# OneWireGateway_2x_0_2.net
KiCad netlist of a schematic drawn in EAGLE
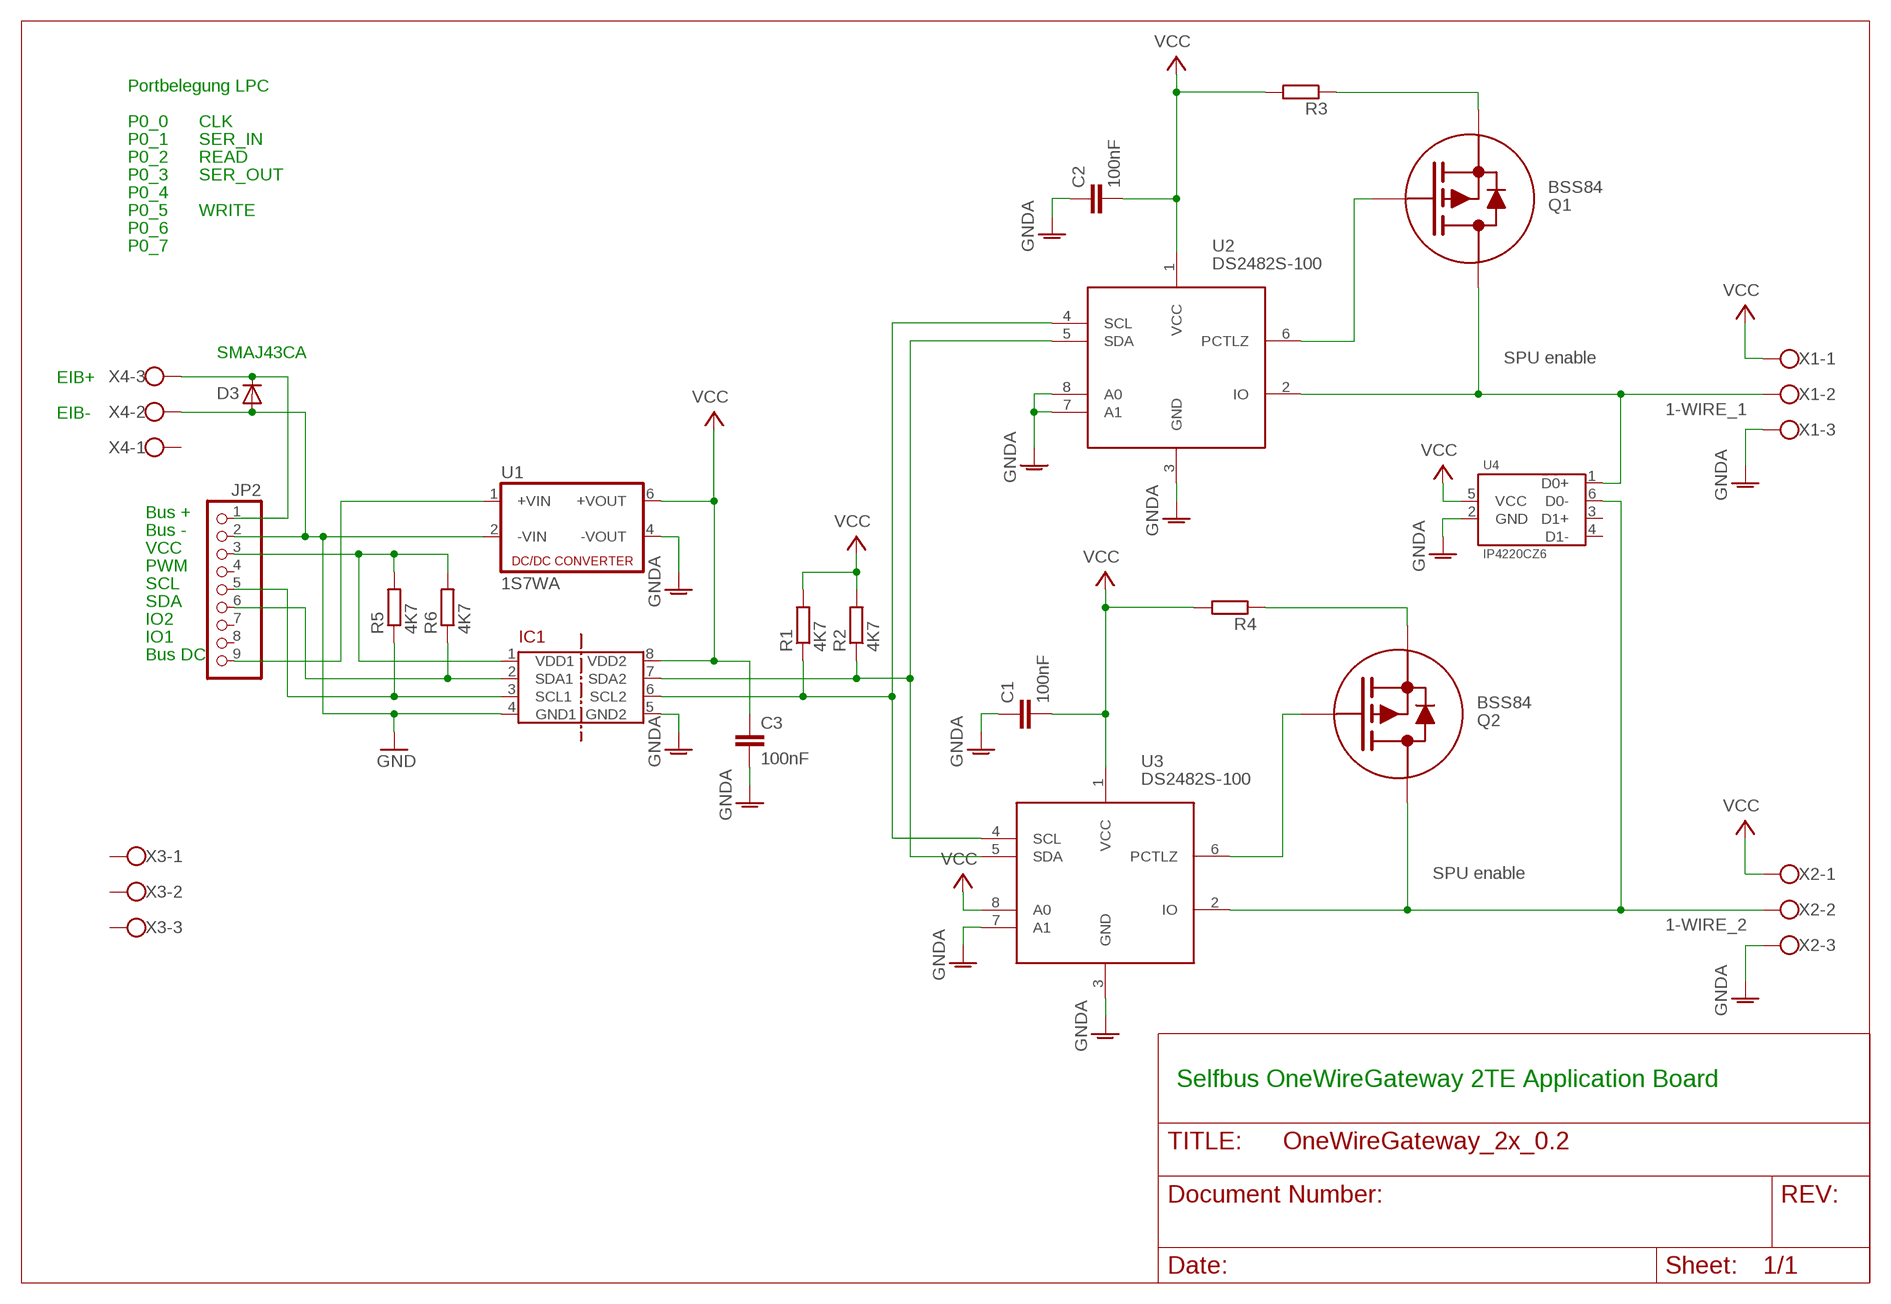
[diagram p0: schematic, sheet 1]

(export (version "E")
  (design (tool "Eeschema 10.0.6"))
  (components
    (comp (ref "C1")
      (value "100nF")
      (footprint "eagle-import:C0805")
      (libsource (lib "eagle-import") (part "C-EUC0805"))
    )
    (comp (ref "C2")
      (value "100nF")
      (footprint "eagle-import:C0805")
      (libsource (lib "eagle-import") (part "C-EUC0805"))
    )
    (comp (ref "C3")
      (value "100nF")
      (footprint "eagle-import:C0805")
      (libsource (lib "eagle-import") (part "C-EUC0805"))
    )
    (comp (ref "D3")
      (value "D-SMB")
      (footprint "eagle-import:SMB")
      (libsource (lib "eagle-import") (part "D-SMB"))
    )
    (comp (ref "IC1")
      (value "ADUM1250")
      (footprint "eagle-import:SO08")
      (libsource (lib "eagle-import") (part "ADUM1250"))
    )
    (comp (ref "JP2")
      (value "PINHD-1X9")
      (footprint "eagle-import:1X09")
      (libsource (lib "eagle-import") (part "PINHD-1X9"))
    )
    (comp (ref "Q1")
      (value "BSS84")
      (footprint "eagle-import:SOT-23-3")
      (fields (field (name "MF") "Fairchild Semiconductor"))
      (libsource (lib "eagle-import") (part "BSS841"))
    )
    (comp (ref "Q2")
      (value "BSS84")
      (footprint "eagle-import:SOT-23-3")
      (fields (field (name "MF") "Fairchild Semiconductor"))
      (libsource (lib "eagle-import") (part "BSS841"))
    )
    (comp (ref "R1")
      (value "4K7")
      (footprint "eagle-import:R0805")
      (libsource (lib "eagle-import") (part "R-EU_R0805"))
    )
    (comp (ref "R2")
      (value "4K7")
      (footprint "eagle-import:R0805")
      (libsource (lib "eagle-import") (part "R-EU_R0805"))
    )
    (comp (ref "R3")
      (value "R-EU_R0805")
      (footprint "eagle-import:R0805")
      (libsource (lib "eagle-import") (part "R-EU_R0805"))
    )
    (comp (ref "R4")
      (value "R-EU_R0805")
      (footprint "eagle-import:R0805")
      (libsource (lib "eagle-import") (part "R-EU_R0805"))
    )
    (comp (ref "R5")
      (value "4K7")
      (footprint "eagle-import:R0805")
      (libsource (lib "eagle-import") (part "R-EU_R0805"))
    )
    (comp (ref "R6")
      (value "4K7")
      (footprint "eagle-import:R0805")
      (libsource (lib "eagle-import") (part "R-EU_R0805"))
    )
    (comp (ref "U1")
      (value "1S7WA")
      (footprint "eagle-import:7PIN_SIP")
      (libsource (lib "eagle-import") (part "1S7WA"))
    )
    (comp (ref "U2")
      (value "DS2482S-100")
      (footprint "eagle-import:SO8")
      (fields (field (name "MF") "Maxim Integrated") (field (name "MPN") "DS2482-100+"))
      (libsource (lib "eagle-import") (part "DS2482-100+1"))
    )
    (comp (ref "U3")
      (value "DS2482S-100")
      (footprint "eagle-import:SO8")
      (fields (field (name "MF") "Maxim Integrated") (field (name "MPN") "DS2482-100+"))
      (libsource (lib "eagle-import") (part "DS2482-100+1"))
    )
    (comp (ref "U4")
      (value "IP4220CZ6")
      (footprint "eagle-import:SOT-6")
      (libsource (lib "eagle-import") (part "IP4220CZ6"))
    )
    (comp (ref "X1")
      (value "W237-03P")
      (footprint "eagle-import:W237-133")
      (libsource (lib "eagle-import") (part "W237-03P"))
    )
    (comp (ref "X2")
      (value "W237-03P")
      (footprint "eagle-import:W237-133")
      (libsource (lib "eagle-import") (part "W237-03P"))
    )
    (comp (ref "X3")
      (value "W237-3E")
      (footprint "eagle-import:W237-3E")
      (libsource (lib "eagle-import") (part "W237-3E"))
    )
    (comp (ref "X4")
      (value "W237-3E")
      (footprint "eagle-import:W237-3E")
      (libsource (lib "eagle-import") (part "W237-3E"))
    )
  )
  (nets
    (net (code "1") (name "/1-WIRE_1") (class "Default")
      (node (ref "Q1") (pin "3") (pinfunction "D_3") (pintype "bidirectional"))
      (node (ref "U2") (pin "2") (pinfunction "IO_2") (pintype "bidirectional"))
      (node (ref "U4") (pin "1") (pinfunction "D0+_1") (pintype "bidirectional"))
      (node (ref "X1") (pin "2") (pinfunction "KL_2") (pintype "passive"))
    )
    (net (code "2") (name "/1-WIRE_2") (class "Default")
      (node (ref "Q2") (pin "3") (pinfunction "D_3") (pintype "bidirectional"))
      (node (ref "U3") (pin "2") (pinfunction "IO_2") (pintype "bidirectional"))
      (node (ref "U4") (pin "6") (pinfunction "D0-_6") (pintype "bidirectional"))
      (node (ref "X2") (pin "2") (pinfunction "KL_2") (pintype "passive"))
    )
    (net (code "3") (name "GND") (class "Default")
      (node (ref "D3") (pin "2") (pinfunction "A_2") (pintype "passive"))
      (node (ref "IC1") (pin "4") (pinfunction "GND1_4") (pintype "power_in"))
      (node (ref "JP2") (pin "2") (pinfunction "2_2") (pintype "passive"))
      (node (ref "U1") (pin "2") (pinfunction "-VIN_2") (pintype "passive"))
      (node (ref "X4") (pin "2") (pinfunction "KL_2") (pintype "passive"))
    )
    (net (code "4") (name "GNDA") (class "Default")
      (node (ref "C1") (pin "1") (pinfunction "1_1") (pintype "passive"))
      (node (ref "C2") (pin "1") (pinfunction "1_1") (pintype "passive"))
      (node (ref "C3") (pin "2") (pinfunction "2_2") (pintype "passive"))
      (node (ref "IC1") (pin "5") (pinfunction "GND2_5") (pintype "power_in"))
      (node (ref "U1") (pin "4") (pinfunction "-VOUT_4") (pintype "passive"))
      (node (ref "U2") (pin "3") (pinfunction "GND_3") (pintype "bidirectional"))
      (node (ref "U2") (pin "7") (pinfunction "A1_7") (pintype "bidirectional"))
      (node (ref "U2") (pin "8") (pinfunction "A0_8") (pintype "bidirectional"))
      (node (ref "U3") (pin "3") (pinfunction "GND_3") (pintype "bidirectional"))
      (node (ref "U3") (pin "7") (pinfunction "A1_7") (pintype "bidirectional"))
      (node (ref "U4") (pin "2") (pinfunction "GND_2") (pintype "bidirectional"))
      (node (ref "X1") (pin "3") (pinfunction "KL_3") (pintype "passive"))
      (node (ref "X2") (pin "3") (pinfunction "KL_3") (pintype "passive"))
    )
    (net (code "5") (name "Net-(D3-C)") (class "Default")
      (node (ref "D3") (pin "1") (pinfunction "C_1") (pintype "passive"))
      (node (ref "JP2") (pin "1") (pinfunction "1_1") (pintype "passive"))
      (node (ref "X4") (pin "3") (pinfunction "KL_3") (pintype "passive"))
    )
    (net (code "6") (name "Net-(IC1-SCL1)") (class "Default")
      (node (ref "IC1") (pin "3") (pinfunction "SCL1_3") (pintype "bidirectional"))
      (node (ref "JP2") (pin "5") (pinfunction "5_5") (pintype "passive"))
      (node (ref "R5") (pin "1") (pinfunction "1_1") (pintype "passive"))
    )
    (net (code "7") (name "Net-(IC1-SCL2)") (class "Default")
      (node (ref "IC1") (pin "6") (pinfunction "SCL2_6") (pintype "bidirectional"))
      (node (ref "R1") (pin "1") (pinfunction "1_1") (pintype "passive"))
      (node (ref "U2") (pin "4") (pinfunction "SCL_4") (pintype "bidirectional"))
      (node (ref "U3") (pin "4") (pinfunction "SCL_4") (pintype "bidirectional"))
    )
    (net (code "8") (name "Net-(IC1-SDA1)") (class "Default")
      (node (ref "IC1") (pin "2") (pinfunction "SDA1_2") (pintype "bidirectional"))
      (node (ref "JP2") (pin "6") (pinfunction "6_6") (pintype "passive"))
      (node (ref "R6") (pin "1") (pinfunction "1_1") (pintype "passive"))
    )
    (net (code "9") (name "Net-(IC1-SDA2)") (class "Default")
      (node (ref "IC1") (pin "7") (pinfunction "SDA2_7") (pintype "bidirectional"))
      (node (ref "R2") (pin "1") (pinfunction "1_1") (pintype "passive"))
      (node (ref "U2") (pin "5") (pinfunction "SDA_5") (pintype "bidirectional"))
      (node (ref "U3") (pin "5") (pinfunction "SDA_5") (pintype "bidirectional"))
    )
    (net (code "10") (name "Net-(IC1-VDD1)") (class "Default")
      (node (ref "IC1") (pin "1") (pinfunction "VDD1_1") (pintype "power_in"))
      (node (ref "JP2") (pin "3") (pinfunction "3_3") (pintype "passive"))
      (node (ref "R5") (pin "2") (pinfunction "2_2") (pintype "passive"))
      (node (ref "R6") (pin "2") (pinfunction "2_2") (pintype "passive"))
    )
    (net (code "11") (name "Net-(Q1-G)") (class "Default")
      (node (ref "Q1") (pin "1") (pinfunction "G_1") (pintype "bidirectional"))
      (node (ref "U2") (pin "6") (pinfunction "PCTLZ_6") (pintype "bidirectional"))
    )
    (net (code "12") (name "Net-(Q1-S)") (class "Default")
      (node (ref "Q1") (pin "2") (pinfunction "S_2") (pintype "bidirectional"))
      (node (ref "R3") (pin "1") (pinfunction "1_1") (pintype "passive"))
    )
    (net (code "13") (name "Net-(Q2-G)") (class "Default")
      (node (ref "Q2") (pin "1") (pinfunction "G_1") (pintype "bidirectional"))
      (node (ref "U3") (pin "6") (pinfunction "PCTLZ_6") (pintype "bidirectional"))
    )
    (net (code "14") (name "Net-(Q2-S)") (class "Default")
      (node (ref "Q2") (pin "2") (pinfunction "S_2") (pintype "bidirectional"))
      (node (ref "R4") (pin "1") (pinfunction "1_1") (pintype "passive"))
    )
    (net (code "15") (name "Net-(U1-+VIN)") (class "Default")
      (node (ref "JP2") (pin "9") (pinfunction "9_9") (pintype "passive"))
      (node (ref "U1") (pin "1") (pinfunction "+VIN_1") (pintype "passive"))
    )
    (net (code "16") (name "VCC") (class "Default")
      (node (ref "C1") (pin "2") (pinfunction "2_2") (pintype "passive"))
      (node (ref "C2") (pin "2") (pinfunction "2_2") (pintype "passive"))
      (node (ref "C3") (pin "1") (pinfunction "1_1") (pintype "passive"))
      (node (ref "IC1") (pin "8") (pinfunction "VDD2_8") (pintype "power_in"))
      (node (ref "R1") (pin "2") (pinfunction "2_2") (pintype "passive"))
      (node (ref "R2") (pin "2") (pinfunction "2_2") (pintype "passive"))
      (node (ref "R3") (pin "2") (pinfunction "2_2") (pintype "passive"))
      (node (ref "R4") (pin "2") (pinfunction "2_2") (pintype "passive"))
      (node (ref "U1") (pin "6") (pinfunction "+VOUT_6") (pintype "passive"))
      (node (ref "U2") (pin "1") (pinfunction "VCC_1") (pintype "bidirectional"))
      (node (ref "U3") (pin "1") (pinfunction "VCC_1") (pintype "bidirectional"))
      (node (ref "U3") (pin "8") (pinfunction "A0_8") (pintype "bidirectional"))
      (node (ref "U4") (pin "5") (pinfunction "VCC_5") (pintype "bidirectional"))
      (node (ref "X1") (pin "1") (pinfunction "KL_1") (pintype "passive"))
      (node (ref "X2") (pin "1") (pinfunction "KL_1") (pintype "passive"))
    )
    (net (code "17") (name "unconnected-(JP2-Pad4)") (class "Default")
      (node (ref "JP2") (pin "4") (pinfunction "4_4") (pintype "passive"))
    )
    (net (code "18") (name "unconnected-(JP2-Pad7)") (class "Default")
      (node (ref "JP2") (pin "7") (pinfunction "7_7") (pintype "passive"))
    )
    (net (code "19") (name "unconnected-(JP2-Pad8)") (class "Default")
      (node (ref "JP2") (pin "8") (pinfunction "8_8") (pintype "passive"))
    )
    (net (code "20") (name "unconnected-(U4-D1+-Pad3)") (class "Default")
      (node (ref "U4") (pin "3") (pinfunction "D1+_3") (pintype "bidirectional"))
    )
    (net (code "21") (name "unconnected-(U4-D1--Pad4)") (class "Default")
      (node (ref "U4") (pin "4") (pinfunction "D1-_4") (pintype "bidirectional"))
    )
    (net (code "22") (name "unconnected-(X3A-KL-Pad1)") (class "Default")
      (node (ref "X3") (pin "1") (pinfunction "KL_1") (pintype "passive"))
    )
    (net (code "23") (name "unconnected-(X3B-KL-Pad2)") (class "Default")
      (node (ref "X3") (pin "2") (pinfunction "KL_2") (pintype "passive"))
    )
    (net (code "24") (name "unconnected-(X3C-KL-Pad3)") (class "Default")
      (node (ref "X3") (pin "3") (pinfunction "KL_3") (pintype "passive"))
    )
    (net (code "25") (name "unconnected-(X4A-KL-Pad1)") (class "Default")
      (node (ref "X4") (pin "1") (pinfunction "KL_1") (pintype "passive"))
    )
  )
)
